# CurrentSenseAmplfier.net
KiCad netlist of a schematic drawn in EasyEDA Pro
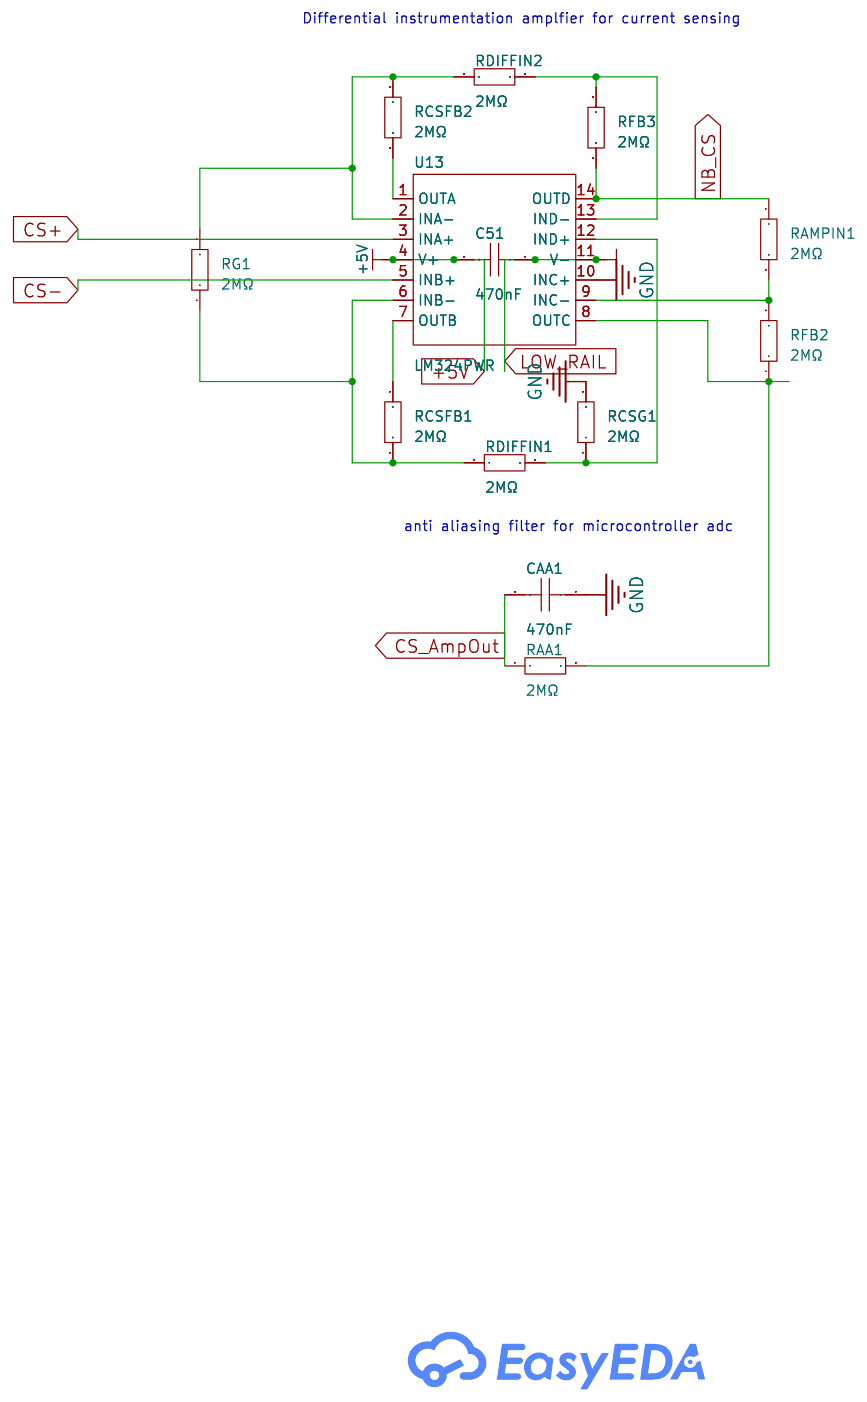
[diagram p0: schematic sheet]

(export (version "E")
  (design (tool "Eeschema 10.0.6"))
  (components
    (comp (ref "C51")
      (value "470nF")
      (footprint "easyedapro:CAP-TH_L7.2-W2.5-P5.00-D0.5")
      (fields
        (field (name "Manufacturer Part") "C241J474J20C000")
        (field (name "Manufacturer") "faratronic(厦门法拉)")
      )
      (libsource (lib "easyedapro") (part "C241J474J20C000"))
    )
    (comp (ref "CAA1")
      (value "470nF")
      (footprint "easyedapro:CAP-TH_L7.2-W2.5-P5.00-D0.5")
      (fields
        (field (name "Manufacturer Part") "C241J474J20C000")
        (field (name "Manufacturer") "faratronic(厦门法拉)")
      )
      (libsource (lib "easyedapro") (part "C241J474J20C000"))
    )
    (comp (ref "RAA1")
      (value "2MΩ")
      (fields (field (name "Manufacturer Part") "SCR0805J2M") (field (name "Manufacturer") "VO(翔胜)"))
      (libsource (lib "easyedapro") (part "Res"))
    )
    (comp (ref "RAMPIN1")
      (value "2MΩ")
      (fields (field (name "Manufacturer Part") "SCR0805J2M") (field (name "Manufacturer") "VO(翔胜)"))
      (libsource (lib "easyedapro") (part "Res"))
    )
    (comp (ref "RCSFB1")
      (value "2MΩ")
      (fields (field (name "Manufacturer Part") "SCR0805J2M") (field (name "Manufacturer") "VO(翔胜)"))
      (libsource (lib "easyedapro") (part "Res"))
    )
    (comp (ref "RCSFB2")
      (value "2MΩ")
      (fields (field (name "Manufacturer Part") "SCR0805J2M") (field (name "Manufacturer") "VO(翔胜)"))
      (libsource (lib "easyedapro") (part "Res"))
    )
    (comp (ref "RCSG1")
      (value "2MΩ")
      (fields (field (name "Manufacturer Part") "SCR0805J2M") (field (name "Manufacturer") "VO(翔胜)"))
      (libsource (lib "easyedapro") (part "Res"))
    )
    (comp (ref "RDIFFIN1")
      (value "2MΩ")
      (fields (field (name "Manufacturer Part") "SCR0805J2M") (field (name "Manufacturer") "VO(翔胜)"))
      (libsource (lib "easyedapro") (part "Res"))
    )
    (comp (ref "RDIFFIN2")
      (value "2MΩ")
      (fields (field (name "Manufacturer Part") "SCR0805J2M") (field (name "Manufacturer") "VO(翔胜)"))
      (libsource (lib "easyedapro") (part "Res"))
    )
    (comp (ref "RFB2")
      (value "2MΩ")
      (fields (field (name "Manufacturer Part") "SCR0805J2M") (field (name "Manufacturer") "VO(翔胜)"))
      (libsource (lib "easyedapro") (part "Res"))
    )
    (comp (ref "RFB3")
      (value "2MΩ")
      (fields (field (name "Manufacturer Part") "SCR0805J2M") (field (name "Manufacturer") "VO(翔胜)"))
      (libsource (lib "easyedapro") (part "Res"))
    )
    (comp (ref "RG1")
      (value "2MΩ")
      (fields (field (name "Manufacturer Part") "SCR0805J2M") (field (name "Manufacturer") "VO(翔胜)"))
      (libsource (lib "easyedapro") (part "Res"))
    )
    (comp (ref "U13")
      (value "LM324PWR")
      (footprint "easyedapro:TSSOP-14_L5.0-W4.4-P0.65-LS6.4-BL")
      (fields (field (name "Manufacturer") "TI(德州仪器)"))
      (libsource (lib "easyedapro") (part "LM324PWR"))
    )
  )
  (nets
    (net (code "1") (name "+5V") (class "Default")
      (node (ref "C51") (pin "2") (pinfunction "2_2") (pintype "unspecified"))
      (node (ref "U13") (pin "4") (pinfunction "V+_4") (pintype "unspecified"))
    )
    (net (code "2") (name "CS+") (class "Default")
      (node (ref "U13") (pin "3") (pinfunction "INA+_3") (pintype "unspecified"))
    )
    (net (code "3") (name "CS-") (class "Default")
      (node (ref "U13") (pin "5") (pinfunction "INB+_5") (pintype "unspecified"))
    )
    (net (code "4") (name "CS_AmpOut") (class "Default")
      (node (ref "CAA1") (pin "2") (pinfunction "2_2") (pintype "unspecified"))
      (node (ref "RAA1") (pin "1") (pinfunction "1_1") (pintype "input"))
    )
    (net (code "5") (name "GND") (class "Default")
      (node (ref "CAA1") (pin "1") (pinfunction "1_1") (pintype "unspecified"))
      (node (ref "RCSG1") (pin "2") (pinfunction "2_2") (pintype "input"))
      (node (ref "U13") (pin "10") (pinfunction "INC+_10") (pintype "unspecified"))
    )
    (net (code "6") (name "LOW_RAIL") (class "Default")
      (node (ref "C51") (pin "1") (pinfunction "1_1") (pintype "unspecified"))
      (node (ref "U13") (pin "11") (pinfunction "V-_11") (pintype "unspecified"))
    )
    (net (code "7") (name "NB_CS") (class "Default")
      (node (ref "RAMPIN1") (pin "1") (pinfunction "1_1") (pintype "input"))
      (node (ref "RFB3") (pin "1") (pinfunction "1_1") (pintype "input"))
      (node (ref "U13") (pin "14") (pinfunction "OUTD_14") (pintype "unspecified"))
    )
    (net (code "8") (name "Net-(U13-INA-)") (class "Default")
      (node (ref "RCSFB2") (pin "1") (pinfunction "1_1") (pintype "input"))
      (node (ref "RDIFFIN2") (pin "1") (pinfunction "1_1") (pintype "input"))
      (node (ref "RG1") (pin "2") (pinfunction "2_2") (pintype "input"))
      (node (ref "U13") (pin "2") (pinfunction "INA-_2") (pintype "unspecified"))
    )
    (net (code "9") (name "Net-(U13-INB-)") (class "Default")
      (node (ref "RCSFB1") (pin "2") (pinfunction "2_2") (pintype "input"))
      (node (ref "RDIFFIN1") (pin "1") (pinfunction "1_1") (pintype "input"))
      (node (ref "RG1") (pin "1") (pinfunction "1_1") (pintype "input"))
      (node (ref "U13") (pin "6") (pinfunction "INB-_6") (pintype "unspecified"))
    )
    (net (code "10") (name "Net-(U13-INC-)") (class "Default")
      (node (ref "RAMPIN1") (pin "2") (pinfunction "2_2") (pintype "input"))
      (node (ref "RFB2") (pin "2") (pinfunction "2_2") (pintype "input"))
      (node (ref "U13") (pin "9") (pinfunction "INC-_9") (pintype "unspecified"))
    )
    (net (code "11") (name "Net-(U13-IND+)") (class "Default")
      (node (ref "RCSG1") (pin "1") (pinfunction "1_1") (pintype "input"))
      (node (ref "RDIFFIN1") (pin "2") (pinfunction "2_2") (pintype "input"))
      (node (ref "U13") (pin "12") (pinfunction "IND+_12") (pintype "unspecified"))
    )
    (net (code "12") (name "Net-(U13-IND-)") (class "Default")
      (node (ref "RDIFFIN2") (pin "2") (pinfunction "2_2") (pintype "input"))
      (node (ref "RFB3") (pin "2") (pinfunction "2_2") (pintype "input"))
      (node (ref "U13") (pin "13") (pinfunction "IND-_13") (pintype "unspecified"))
    )
    (net (code "13") (name "Net-(U13-OUTA)") (class "Default")
      (node (ref "RCSFB2") (pin "2") (pinfunction "2_2") (pintype "input"))
      (node (ref "U13") (pin "1") (pinfunction "OUTA_1") (pintype "unspecified"))
    )
    (net (code "14") (name "Net-(U13-OUTB)") (class "Default")
      (node (ref "RCSFB1") (pin "1") (pinfunction "1_1") (pintype "input"))
      (node (ref "U13") (pin "7") (pinfunction "OUTB_7") (pintype "unspecified"))
    )
    (net (code "15") (name "Net-(U13-OUTC)") (class "Default")
      (node (ref "RAA1") (pin "2") (pinfunction "2_2") (pintype "input"))
      (node (ref "RFB2") (pin "1") (pinfunction "1_1") (pintype "input"))
      (node (ref "U13") (pin "8") (pinfunction "OUTC_8") (pintype "unspecified"))
    )
  )
)
